# CH32V007K8U-R0.net
KiCad netlist of a schematic drawn in Altium Designer
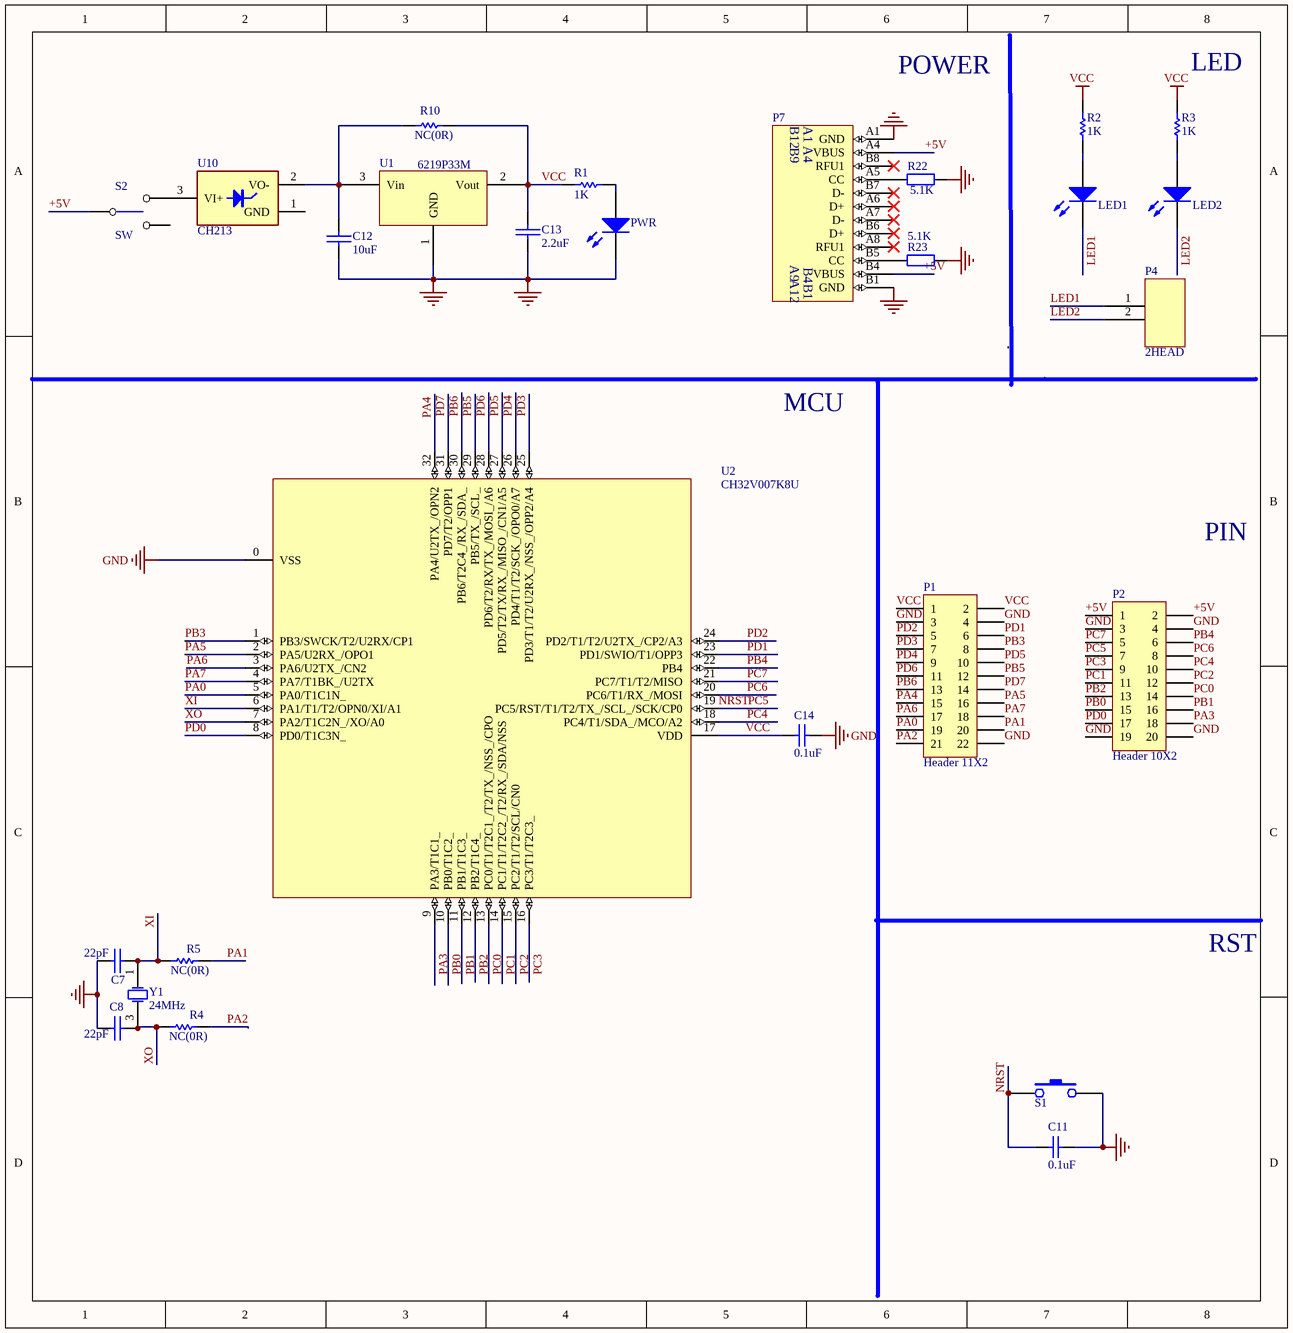
[diagram p0: CH32V007K8U-R0.SchDoc]

(export (version "E")
  (design (tool "Eeschema 10.0.6"))
  (components
    (comp (ref "C7")
      (value "22pF")
      (footprint "0402_C")
      (description "Capacitor")
      (libsource (lib "*") (part "CAP"))
    )
    (comp (ref "C8")
      (value "22pF")
      (footprint "0402_C")
      (description "Capacitor")
      (libsource (lib "*") (part "CAP"))
    )
    (comp (ref "C11")
      (value "0.1uF")
      (footprint "0402_C")
      (description "Capacitor")
      (fields (field (name "PUBLISHER") "Altium Limited"))
      (libsource (lib "*") (part "Cap"))
    )
    (comp (ref "C12")
      (value "10uF")
      (footprint "0603_C")
      (description "Capacitor")
      (libsource (lib "wch_sch_others") (part "CAP"))
    )
    (comp (ref "C13")
      (value "2.2uF")
      (footprint "0402_C")
      (description "Capacitor")
      (libsource (lib "wch_sch_others") (part "CAP"))
    )
    (comp (ref "C14")
      (value "0.1uF")
      (footprint "0402_C")
      (description "Capacitor")
      (fields (field (name "PUBLISHER") "Altium Limited"))
      (libsource (lib "*") (part "Cap"))
    )
    (comp (ref "LED1")
      (value "LED1   blue")
      (footprint "0603+")
      (description "Typical INFRARED GaAs LED")
      (fields (field (name "PUBLISHER") "Altium Limited"))
      (libsource (lib "*") (part "LED0"))
    )
    (comp (ref "LED2")
      (value "LED2  blue")
      (footprint "0603+")
      (description "Typical INFRARED GaAs LED")
      (fields (field (name "PUBLISHER") "Altium Limited"))
      (libsource (lib "*") (part "LED0"))
    )
    (comp (ref "P1")
      (value "Header 11X2")
      (footprint "IDC22-2.54mm")
      (description "Header, 11-Pin, Dual row")
      (fields (field (name "PUBLISHER") "Altium Limited"))
      (libsource (lib "Miscellaneous Connectors") (part "Header 11X2"))
    )
    (comp (ref "P2")
      (value "Header 10X2")
      (footprint "IDC20-2.54mm")
      (description "Header, 10-Pin, Dual row")
      (fields (field (name "PUBLISHER") "Altium Limited"))
      (libsource (lib "Miscellaneous Connectors") (part "Header 10X2"))
    )
    (comp (ref "P4") (value "2HEAD") (footprint "SIP2-2.54mm") (libsource (lib "*") (part "2HEAD")))
    (comp (ref "P7")
      (value "TYPE-C")
      (footprint "TYPE-C-Receptacle-2.0")
      (libsource (lib "*") (part "TYPE-C1"))
    )
    (comp (ref "PWR")
      (value "POWER  red")
      (footprint "0603+")
      (description "Typical INFRARED GaAs LED")
      (fields (field (name "PUBLISHER") "Altium Limited"))
      (libsource (lib "") (part "LED0_1"))
    )
    (comp (ref "R1")
      (value "1K")
      (footprint "0402")
      (description "Semiconductor Resistor")
      (fields (field (name "PUBLISHER") "Altium Limited"))
      (libsource (lib "*") (part "Res Semi"))
    )
    (comp (ref "R2")
      (value "1K")
      (footprint "0402")
      (description "Semiconductor Resistor")
      (fields (field (name "PUBLISHER") "Altium Limited"))
      (libsource (lib "*") (part "Res Semi"))
    )
    (comp (ref "R3")
      (value "1K")
      (footprint "0402")
      (description "Semiconductor Resistor")
      (fields (field (name "PUBLISHER") "Altium Limited"))
      (libsource (lib "*") (part "Res Semi"))
    )
    (comp (ref "R4")
      (value "NC(0R)")
      (footprint "0402")
      (description "Semiconductor Resistor")
      (fields (field (name "Comment") "0R") (field (name "PUBLISHER") "Altium Limited"))
      (libsource (lib "*") (part "Res Semi"))
    )
    (comp (ref "R5")
      (value "NC(0R)")
      (footprint "0402")
      (description "Semiconductor Resistor")
      (fields (field (name "Comment") "0R") (field (name "PUBLISHER") "Altium Limited"))
      (libsource (lib "*") (part "Res Semi"))
    )
    (comp (ref "R10")
      (value "NC(0R)")
      (footprint "0402")
      (description "Semiconductor Resistor")
      (fields (field (name "Comment") "0R") (field (name "PUBLISHER") "Altium Limited"))
      (libsource (lib "*") (part "Res Semi"))
    )
    (comp (ref "R22")
      (value "5.1K")
      (footprint "0402")
      (description "Resistor")
      (libsource (lib "Miscellaneous Devices") (part "Res2"))
    )
    (comp (ref "R23")
      (value "5.1K")
      (footprint "0402")
      (description "Resistor")
      (libsource (lib "Miscellaneous Devices") (part "Res2"))
    )
    (comp (ref "S1") (value "NRST") (footprint "SMD_6.1x3.65x2.5mm-KEY") (libsource (lib "*") (part "KEY")))
    (comp (ref "S2") (value "SW") (footprint "SW1") (libsource (lib "*") (part "SW")))
    (comp (ref "U1")
      (value "6219P33M")
      (footprint "SOT-23")
      (libsource (lib "wch_sch_others") (part "6219P33M"))
    )
    (comp (ref "U2")
      (value "CH32V007K8U")
      (footprint "QFN32_4X4")
      (description "RISC-V MCU, ADC/OPA/CMP/2*UART/I2C/SPI")
      (libsource (lib "CHXXX(2)") (part "CH32V007K8U6"))
    )
    (comp (ref "U10")
      (value "CH213")
      (footprint "SOT-23-3")
      (description "Ideal Diode 5V*1A")
      (libsource (lib "CHXXX") (part "CH213E"))
    )
    (comp (ref "Y1")
      (value "24MHz")
      (footprint "XT3225")
      (description "Crystal Oscillator")
      (fields (field (name "PUBLISHER") "Altium Limited"))
      (libsource (lib "*") (part "XTAL"))
    )
  )
  (nets
    (net (code "1") (name "/+5V") (class "Default")
      (node (ref "P2") (pin "1") (pinfunction "1_1") (pintype "passive"))
      (node (ref "P2") (pin "2") (pinfunction "2_2") (pintype "passive"))
      (node (ref "P7") (pin "A4") (pinfunction "VBUS_A4") (pintype "bidirectional"))
      (node (ref "P7") (pin "B4") (pinfunction "VBUS_B4") (pintype "bidirectional"))
      (node (ref "S2") (pin "1") (pinfunction "1_1") (pintype "passive"))
    )
    (net (code "2") (name "/LED1") (class "Default")
      (node (ref "LED1") (pin "2") (pinfunction "K_2") (pintype "passive"))
      (node (ref "P4") (pin "1") (pintype "passive"))
    )
    (net (code "3") (name "/LED2") (class "Default")
      (node (ref "LED2") (pin "2") (pinfunction "K_2") (pintype "passive"))
      (node (ref "P4") (pin "2") (pintype "passive"))
    )
    (net (code "4") (name "/NRST") (class "Default")
      (node (ref "C11") (pin "2") (pinfunction "2_2") (pintype "passive"))
      (node (ref "P2") (pin "7") (pinfunction "7_7") (pintype "passive"))
      (node (ref "S1") (pin "1") (pinfunction "1_1") (pintype "passive"))
      (node (ref "U2") (pin "19") (pinfunction "PC5/RST/T1/T2/TX_/SCL_/SCK/CP0_19") (pintype "bidirectional"))
    )
    (net (code "5") (name "/PA0") (class "Default")
      (node (ref "P1") (pin "19") (pinfunction "19_19") (pintype "passive"))
      (node (ref "U2") (pin "5") (pinfunction "PA0/T1C1N__5") (pintype "bidirectional"))
    )
    (net (code "6") (name "/PA1") (class "Default")
      (node (ref "P1") (pin "20") (pinfunction "20_20") (pintype "passive"))
      (node (ref "R5") (pin "2") (pinfunction "2_2") (pintype "passive"))
    )
    (net (code "7") (name "/PA2") (class "Default")
      (node (ref "P1") (pin "21") (pinfunction "21_21") (pintype "passive"))
      (node (ref "R4") (pin "2") (pinfunction "2_2") (pintype "passive"))
    )
    (net (code "8") (name "/PA3") (class "Default")
      (node (ref "P2") (pin "18") (pinfunction "18_18") (pintype "passive"))
      (node (ref "U2") (pin "9") (pinfunction "PA3/T1C1__9") (pintype "bidirectional"))
    )
    (net (code "9") (name "/PA4") (class "Default")
      (node (ref "P1") (pin "15") (pinfunction "15_15") (pintype "passive"))
      (node (ref "U2") (pin "32") (pinfunction "PA4/U2TX_/OPN2_32") (pintype "bidirectional"))
    )
    (net (code "10") (name "/PA5") (class "Default")
      (node (ref "P1") (pin "16") (pinfunction "16_16") (pintype "passive"))
      (node (ref "U2") (pin "2") (pinfunction "PA5/U2RX_/OPO1_2") (pintype "bidirectional"))
    )
    (net (code "11") (name "/PA6") (class "Default")
      (node (ref "P1") (pin "17") (pinfunction "17_17") (pintype "passive"))
      (node (ref "U2") (pin "3") (pinfunction "PA6/U2TX_/CN2_3") (pintype "bidirectional"))
    )
    (net (code "12") (name "/PA7") (class "Default")
      (node (ref "P1") (pin "18") (pinfunction "18_18") (pintype "passive"))
      (node (ref "U2") (pin "4") (pinfunction "PA7/T1BK_/U2TX_4") (pintype "bidirectional"))
    )
    (net (code "13") (name "/PB0") (class "Default")
      (node (ref "P2") (pin "15") (pinfunction "15_15") (pintype "passive"))
      (node (ref "U2") (pin "10") (pinfunction "PB0/T1C2__10") (pintype "bidirectional"))
    )
    (net (code "14") (name "/PB1") (class "Default")
      (node (ref "P2") (pin "16") (pinfunction "16_16") (pintype "passive"))
      (node (ref "U2") (pin "11") (pinfunction "PB1/T1C3__11") (pintype "bidirectional"))
    )
    (net (code "15") (name "/PB2") (class "Default")
      (node (ref "P2") (pin "13") (pinfunction "13_13") (pintype "passive"))
      (node (ref "U2") (pin "12") (pinfunction "PB2/T1C4__12") (pintype "bidirectional"))
    )
    (net (code "16") (name "/PB3") (class "Default")
      (node (ref "P1") (pin "8") (pinfunction "8_8") (pintype "passive"))
      (node (ref "U2") (pin "1") (pinfunction "PB3/SWCK/T2/U2RX/CP1_1") (pintype "bidirectional"))
    )
    (net (code "17") (name "/PB4") (class "Default")
      (node (ref "P2") (pin "6") (pinfunction "6_6") (pintype "passive"))
      (node (ref "U2") (pin "22") (pinfunction "PB4_22") (pintype "bidirectional"))
    )
    (net (code "18") (name "/PB5") (class "Default")
      (node (ref "P1") (pin "12") (pinfunction "12_12") (pintype "passive"))
      (node (ref "U2") (pin "29") (pinfunction "PB5/TX_/SCL__29") (pintype "bidirectional"))
    )
    (net (code "19") (name "/PB6") (class "Default")
      (node (ref "P1") (pin "13") (pinfunction "13_13") (pintype "passive"))
      (node (ref "U2") (pin "30") (pinfunction "PB6/T2C4_/RX_/SDA__30") (pintype "bidirectional"))
    )
    (net (code "20") (name "/PC0") (class "Default")
      (node (ref "P2") (pin "14") (pinfunction "14_14") (pintype "passive"))
      (node (ref "U2") (pin "13") (pinfunction "PC0/T1/T2C1_/T2/TX_/NSS_/CPO_13") (pintype "bidirectional"))
    )
    (net (code "21") (name "/PC1") (class "Default")
      (node (ref "P2") (pin "11") (pinfunction "11_11") (pintype "passive"))
      (node (ref "U2") (pin "14") (pinfunction "PC1/T1/T2C2_/T2/RX_/SDA/NSS_14") (pintype "bidirectional"))
    )
    (net (code "22") (name "/PC2") (class "Default")
      (node (ref "P2") (pin "12") (pinfunction "12_12") (pintype "passive"))
      (node (ref "U2") (pin "15") (pinfunction "PC2/T1/T2/SCL/CN0_15") (pintype "bidirectional"))
    )
    (net (code "23") (name "/PC3") (class "Default")
      (node (ref "P2") (pin "9") (pinfunction "9_9") (pintype "passive"))
      (node (ref "U2") (pin "16") (pinfunction "PC3/T1/T2C3__16") (pintype "bidirectional"))
    )
    (net (code "24") (name "/PC4") (class "Default")
      (node (ref "P2") (pin "10") (pinfunction "10_10") (pintype "passive"))
      (node (ref "U2") (pin "18") (pinfunction "PC4/T1/SDA_/MCO/A2_18") (pintype "bidirectional"))
    )
    (net (code "25") (name "/PC6") (class "Default")
      (node (ref "P2") (pin "8") (pinfunction "8_8") (pintype "passive"))
      (node (ref "U2") (pin "20") (pinfunction "PC6/T1/RX_/MOSI_20") (pintype "bidirectional"))
    )
    (net (code "26") (name "/PC7") (class "Default")
      (node (ref "P2") (pin "5") (pinfunction "5_5") (pintype "passive"))
      (node (ref "U2") (pin "21") (pinfunction "PC7/T1/T2/MISO_21") (pintype "bidirectional"))
    )
    (net (code "27") (name "/PD0") (class "Default")
      (node (ref "P2") (pin "17") (pinfunction "17_17") (pintype "passive"))
      (node (ref "U2") (pin "8") (pinfunction "PD0/T1C3N__8") (pintype "bidirectional"))
    )
    (net (code "28") (name "/PD1") (class "Default")
      (node (ref "P1") (pin "6") (pinfunction "6_6") (pintype "passive"))
      (node (ref "U2") (pin "23") (pinfunction "PD1/SWIO/T1/OPP3_23") (pintype "bidirectional"))
    )
    (net (code "29") (name "/PD2") (class "Default")
      (node (ref "P1") (pin "5") (pinfunction "5_5") (pintype "passive"))
      (node (ref "U2") (pin "24") (pinfunction "PD2/T1/T2/U2TX_/CP2/A3_24") (pintype "bidirectional"))
    )
    (net (code "30") (name "/PD3") (class "Default")
      (node (ref "P1") (pin "7") (pinfunction "7_7") (pintype "passive"))
      (node (ref "U2") (pin "25") (pinfunction "PD3/T1/T2/U2RX_/NSS_/OPP2/A4_25") (pintype "bidirectional"))
    )
    (net (code "31") (name "/PD4") (class "Default")
      (node (ref "P1") (pin "9") (pinfunction "9_9") (pintype "passive"))
      (node (ref "U2") (pin "26") (pinfunction "PD4/T1/T2/SCK_/OPO0/A7_26") (pintype "bidirectional"))
    )
    (net (code "32") (name "/PD5") (class "Default")
      (node (ref "P1") (pin "10") (pinfunction "10_10") (pintype "passive"))
      (node (ref "U2") (pin "27") (pinfunction "PD5/T2/TX/RX_/MISO_/CN1/A5_27") (pintype "bidirectional"))
    )
    (net (code "33") (name "/PD6") (class "Default")
      (node (ref "P1") (pin "11") (pinfunction "11_11") (pintype "passive"))
      (node (ref "U2") (pin "28") (pinfunction "PD6/T2/RX/TX_/MOSI_/A6_28") (pintype "bidirectional"))
    )
    (net (code "34") (name "/PD7") (class "Default")
      (node (ref "P1") (pin "14") (pinfunction "14_14") (pintype "passive"))
      (node (ref "U2") (pin "31") (pinfunction "PD7/T2/OPP1_31") (pintype "bidirectional"))
    )
    (net (code "35") (name "/XI") (class "Default")
      (node (ref "C7") (pin "2") (pinfunction "2_2") (pintype "passive"))
      (node (ref "R5") (pin "1") (pinfunction "1_1") (pintype "passive"))
      (node (ref "U2") (pin "6") (pinfunction "PA1/T1/T2/OPN0/XI/A1_6") (pintype "bidirectional"))
      (node (ref "Y1") (pin "1") (pinfunction "OSC1_1") (pintype "passive"))
    )
    (net (code "36") (name "/XO") (class "Default")
      (node (ref "C8") (pin "2") (pinfunction "2_2") (pintype "passive"))
      (node (ref "R4") (pin "1") (pinfunction "1_1") (pintype "passive"))
      (node (ref "U2") (pin "7") (pinfunction "PA2/T1C2N_/XO/A0_7") (pintype "bidirectional"))
      (node (ref "Y1") (pin "3") (pinfunction "OSC2_3") (pintype "passive"))
    )
    (net (code "37") (name "GND") (class "Default")
      (node (ref "C11") (pin "1") (pinfunction "1_1") (pintype "passive"))
      (node (ref "C12") (pin "2") (pinfunction "2_2") (pintype "passive"))
      (node (ref "C13") (pin "1") (pinfunction "1_1") (pintype "passive"))
      (node (ref "C14") (pin "2") (pinfunction "2_2") (pintype "passive"))
      (node (ref "C7") (pin "1") (pinfunction "1_1") (pintype "passive"))
      (node (ref "C8") (pin "1") (pinfunction "1_1") (pintype "passive"))
      (node (ref "P1") (pin "22") (pinfunction "22_22") (pintype "passive"))
      (node (ref "P1") (pin "3") (pinfunction "3_3") (pintype "passive"))
      (node (ref "P1") (pin "4") (pinfunction "4_4") (pintype "passive"))
      (node (ref "P2") (pin "19") (pinfunction "19_19") (pintype "passive"))
      (node (ref "P2") (pin "20") (pinfunction "20_20") (pintype "passive"))
      (node (ref "P2") (pin "3") (pinfunction "3_3") (pintype "passive"))
      (node (ref "P2") (pin "4") (pinfunction "4_4") (pintype "passive"))
      (node (ref "P7") (pin "A1") (pinfunction "GND_A1") (pintype "bidirectional"))
      (node (ref "P7") (pin "B1") (pinfunction "GND_B1") (pintype "bidirectional"))
      (node (ref "PWR") (pin "2") (pinfunction "K_2") (pintype "passive"))
      (node (ref "R22") (pin "2") (pinfunction "2_2") (pintype "passive"))
      (node (ref "R23") (pin "2") (pinfunction "2_2") (pintype "passive"))
      (node (ref "S1") (pin "2") (pinfunction "2_2") (pintype "passive"))
      (node (ref "U1") (pin "1") (pinfunction "GND_1") (pintype "passive"))
      (node (ref "U2") (pin "0") (pinfunction "VSS_0") (pintype "power_in"))
    )
    (net (code "38") (name "Net-(LED1-A)") (class "Default")
      (node (ref "LED1") (pin "1") (pinfunction "A_1") (pintype "passive"))
      (node (ref "R2") (pin "2") (pinfunction "2_2") (pintype "passive"))
    )
    (net (code "39") (name "Net-(LED2-A)") (class "Default")
      (node (ref "LED2") (pin "1") (pinfunction "A_1") (pintype "passive"))
      (node (ref "R3") (pin "2") (pinfunction "2_2") (pintype "passive"))
    )
    (net (code "40") (name "Net-(P7-CC-PadA5)") (class "Default")
      (node (ref "P7") (pin "A5") (pinfunction "CC_A5") (pintype "bidirectional"))
      (node (ref "R22") (pin "1") (pinfunction "1_1") (pintype "passive"))
    )
    (net (code "41") (name "Net-(P7-CC-PadB5)") (class "Default")
      (node (ref "P7") (pin "B5") (pinfunction "CC_B5") (pintype "bidirectional"))
      (node (ref "R23") (pin "1") (pinfunction "1_1") (pintype "passive"))
    )
    (net (code "42") (name "Net-(PWR-A)") (class "Default")
      (node (ref "PWR") (pin "1") (pinfunction "A_1") (pintype "passive"))
      (node (ref "R1") (pin "1") (pinfunction "1_1") (pintype "passive"))
    )
    (net (code "43") (name "Net-(U1-Vin)") (class "Default")
      (node (ref "C12") (pin "1") (pinfunction "1_1") (pintype "passive"))
      (node (ref "R10") (pin "1") (pinfunction "1_1") (pintype "passive"))
      (node (ref "U1") (pin "3") (pinfunction "Vin_3") (pintype "passive"))
      (node (ref "U10") (pin "2") (pinfunction "VO-_2") (pintype "power_in"))
    )
    (net (code "44") (name "Net-(U10-VI+)") (class "Default")
      (node (ref "S2") (pin "3") (pinfunction "3_3") (pintype "passive"))
      (node (ref "U10") (pin "3") (pinfunction "VI+_3") (pintype "power_in"))
    )
    (net (code "45") (name "VCC") (class "Default")
      (node (ref "C13") (pin "2") (pinfunction "2_2") (pintype "passive"))
      (node (ref "C14") (pin "1") (pinfunction "1_1") (pintype "passive"))
      (node (ref "P1") (pin "1") (pinfunction "1_1") (pintype "passive"))
      (node (ref "P1") (pin "2") (pinfunction "2_2") (pintype "passive"))
      (node (ref "R1") (pin "2") (pinfunction "2_2") (pintype "passive"))
      (node (ref "R10") (pin "2") (pinfunction "2_2") (pintype "passive"))
      (node (ref "R2") (pin "1") (pinfunction "1_1") (pintype "passive"))
      (node (ref "R3") (pin "1") (pinfunction "1_1") (pintype "passive"))
      (node (ref "U1") (pin "2") (pinfunction "Vout_2") (pintype "passive"))
      (node (ref "U2") (pin "17") (pinfunction "VDD_17") (pintype "power_in"))
    )
    (net (code "46") (name "unconnected-(P7-D+-PadA6)") (class "Default")
      (node (ref "P7") (pin "A6") (pinfunction "D+_A6") (pintype "bidirectional+no_connect"))
    )
    (net (code "47") (name "unconnected-(P7-D+-PadB6)") (class "Default")
      (node (ref "P7") (pin "B6") (pinfunction "D+_B6") (pintype "bidirectional+no_connect"))
    )
    (net (code "48") (name "unconnected-(P7-D--PadA7)") (class "Default")
      (node (ref "P7") (pin "A7") (pinfunction "D-_A7") (pintype "bidirectional+no_connect"))
    )
    (net (code "49") (name "unconnected-(P7-D--PadB7)") (class "Default")
      (node (ref "P7") (pin "B7") (pinfunction "D-_B7") (pintype "bidirectional+no_connect"))
    )
    (net (code "50") (name "unconnected-(P7-RFU1-PadA8)") (class "Default")
      (node (ref "P7") (pin "A8") (pinfunction "RFU1_A8") (pintype "bidirectional+no_connect"))
    )
    (net (code "51") (name "unconnected-(P7-RFU1-PadB8)") (class "Default")
      (node (ref "P7") (pin "B8") (pinfunction "RFU1_B8") (pintype "bidirectional+no_connect"))
    )
    (net (code "52") (name "unconnected-(S2-Pad2)") (class "Default")
      (node (ref "S2") (pin "2") (pinfunction "2_2") (pintype "passive"))
    )
    (net (code "53") (name "unconnected-(U10-GND-Pad1)") (class "Default")
      (node (ref "U10") (pin "1") (pinfunction "GND_1") (pintype "power_in"))
    )
  )
)
